# Sheet2.net
KiCad netlist of a schematic drawn in Altium Designer
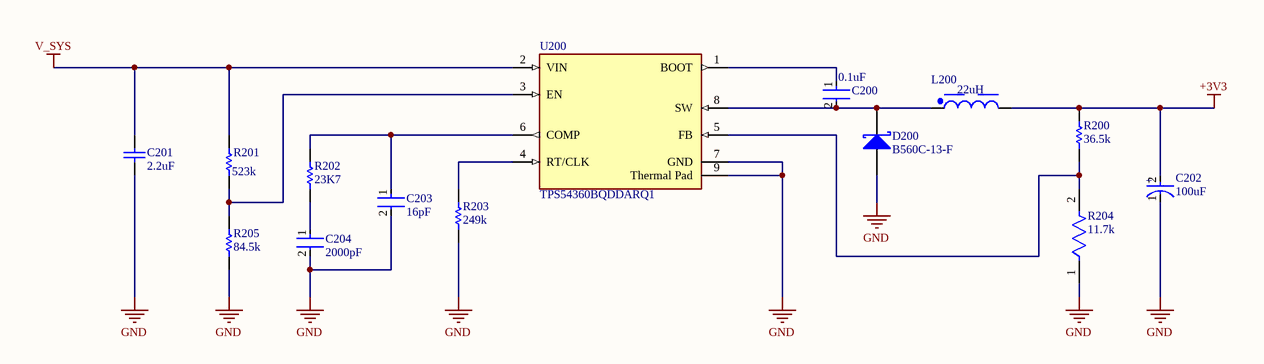
[diagram p0: Sheet2.SchDoc]

(export (version "E")
  (design (tool "Eeschema 10.0.6"))
  (components
    (comp (ref "C200")
      (value "0.1uF")
      (footprint "FP-CC0805-0_85-MFG")
      (description "CAP CER 0.1UF 50V X7R 0805")
      (fields (field (name "TOLERANCE") "0.1") (field (name "MANUFACTURER PART NUMBER") "CC0805KRX7R9BB104"))
      (libsource (lib "Altium Content Vault") (part "11868f565c42a9108669ba33697ecf6"))
    )
    (comp (ref "C201")
      (value "2.2uF")
      (footprint "CAPC3225X250X20LL40")
      (description "Chip Capacitor, 2.2 uF, +/- 10%, -55 to 125 degC, 1210 (3225 Metric), RoHS, Tape and Reel")
      (fields
        (field (name "PCN PART NUMBER") "MLCCPartNumberChange30/Nov/2012")
        (field (name "MANUFACTURER") "TDK")
      )
      (libsource (lib "Altium Content Vault") (part "CAP-NP-2"))
    )
    (comp (ref "C202")
      (value "100uF")
      (footprint "FP-POSCAP-D2E-MFG")
      (description "Molded Tantalum Polymer Capacitor 100uF 20% 6.3V life 2000Hours SMD 2917")
      (fields (field (name "TOLERANCE") "20%") (field (name "VOLTAGE") "6.3V"))
      (libsource (lib "Altium Content Vault") (part "84cdeef69100fe67ea2095257d64e1a"))
    )
    (comp (ref "C203")
      (value "16pF")
      (footprint "FP-C0603C-CF-MFG")
      (description "CAP CER 16PF 50V 5% NP0 0603")
      (fields
        (field (name "MANUFACTURER PART NUMBER") "C0603C160J5GACTU")
        (field (name "OCTOPART") "https://octopart.com/c0603c160j5gactu-kemet-9143816")
      )
      (libsource (lib "Altium Content Vault") (part "b4654b650e69147ec39a6b967a45e02"))
    )
    (comp (ref "C204")
      (value "2000pF")
      (footprint "FP-C0805C-DN-MFG")
      (description "CAP CER 2000PF 25V 5% NP0 0805")
      (fields
        (field (name "OCTOPART") "https://octopart.com/c0805c202j3gactu-kemet-11998870")
        (field (name "MANUFACTURER PART NUMBER") "C0805C202J3GACTU")
      )
      (libsource (lib "Altium Content Vault") (part "b4654b650e69147ec39a6b967a45e02"))
    )
    (comp (ref "D200")
      (value "B560C-13-F")
      (footprint "DIOD-B5X0C-2_M")
      (description "Schottky Barrier Rectifier, 5 A, 60 V, -55 to 125 degC, 2-Pin SMD, RoHS, Tape and Reel")
      (fields (field (name "MANUFACTURER") "DiodesIncorporated"))
      (libsource (lib "Altium Content Vault") (part "DSKY-KA-2"))
    )
    (comp (ref "L200")
      (value "22uH")
      (footprint "WE-TI_8095")
      (description "Inductor, 22Uh, Unshielded, 3A, Rad Rohs Compliant: Yes")
      (libsource (lib "Altium Content Vault") (part "Inductor - 2"))
    )
    (comp (ref "R200")
      (value "36.5k")
      (footprint "RESC0603X28X15ML05T05")
      (description "100mW Thick Film Resistors 75V ±1% ±100ppm/℃ 36.5kΩ 0603 Chip Resistor - Surface")
      (fields (field (name "MANUFACTURER") "Vishay Dale") (field (name "PART NUMBER") "CRCW020136K5FNED"))
      (libsource (lib "Altium Content Vault") (part "RES"))
    )
    (comp (ref "R201")
      (value "523k")
      (footprint "RESC1005X40X25NL05T10")
      (description "RES 523K OHM 1% 1/16W 0402")
      (fields (field (name "PART NUMBER") "RC0402FR-07523KL") (field (name "MANUFACTURER") "Yageo / Phycomp"))
      (libsource (lib "Altium Content Vault") (part "RES"))
    )
    (comp (ref "R202")
      (value "23K7")
      (footprint "RESC0201(0603)_M")
      (description "23K7 0.05W 1% 0201 (0603 Metric)  SMD")
      (fields (field (name "POWER") "0.05 W") (field (name "TOLERANCE") "1 %"))
      (libsource (lib "Altium Content Vault") (part "RES"))
    )
    (comp (ref "R203")
      (value "249k")
      (footprint "RESC0603X28X15LL05T05")
      (description "Res Thick Film 0603 2.2K Ohm 1% 0.1W(1/10W) ±100ppm/C SMD AutomoTEXASve T/R")
      (fields (field (name "PART NUMBER") "CRCW0201249KFKED") (field (name "MANUFACTURER") "Vishay Dale"))
      (libsource (lib "Altium Content Vault") (part "RES"))
    )
    (comp (ref "R204")
      (value "11.7k")
      (footprint "FP-RT0805-MFG")
      (description "RES 11.7K OHM 0.1% 1/8W 0805")
      (fields (field (name "TOLERANCE") "0.1%") (field (name "MANUFACTURER") "Yageo"))
      (libsource (lib "Altium Content Vault") (part "1029c3af85768c4190bb7ad29bc67b5"))
    )
    (comp (ref "R205")
      (value "84.5k")
      (footprint "RESC1005X40X25ML05T10")
      (description "RES 84.5K OHM 1% 1/16W 0402")
      (fields (field (name "MANUFACTURER") "Yageo / Phycomp") (field (name "PART NUMBER") "RC0402FR-0784K5L"))
      (libsource (lib "Altium Content Vault") (part "RES"))
    )
    (comp (ref "U200")
      (value "TPS54360BQDDARQ1")
      (footprint "FP-DDA0008E-MFG")
      (description "IC REG BCK SPLIT RAIL ADJ 8SOPWR")
      (fields
        (field (name "OCTOPART") "https://octopart.com/tps54360bqddarq1-texas+instruments-80336296")
        (field (name "MANUFACTURER") "Texas Instruments")
      )
      (libsource (lib "Altium Content Vault") (part "4212a49dfb3254156d8b0568d0e7c54"))
    )
  )
  (nets
    (net (code "1") (name "+3V3") (class "Default")
      (node (ref "C202") (pin "2") (pinfunction "A_2") (pintype "passive"))
      (node (ref "L200") (pin "2") (pinfunction "2_2") (pintype "passive"))
      (node (ref "R200") (pin "2") (pinfunction "2_2") (pintype "passive"))
    )
    (net (code "2") (name "GND") (class "Default")
      (node (ref "C201") (pin "1") (pinfunction "1_1") (pintype "passive"))
      (node (ref "C202") (pin "1") (pinfunction "C_1") (pintype "passive"))
      (node (ref "C203") (pin "2") (pinfunction "2_2") (pintype "passive"))
      (node (ref "C204") (pin "2") (pinfunction "2_2") (pintype "passive"))
      (node (ref "D200") (pin "2") (pinfunction "A_2") (pintype "passive"))
      (node (ref "R203") (pin "1") (pinfunction "1_1") (pintype "passive"))
      (node (ref "R204") (pin "1") (pinfunction "1_1") (pintype "passive"))
      (node (ref "R205") (pin "1") (pinfunction "1_1") (pintype "passive"))
      (node (ref "U200") (pin "7") (pinfunction "GND_7") (pintype "power_in"))
      (node (ref "U200") (pin "9") (pinfunction "Thermal_Pad_9") (pintype "power_in"))
    )
    (net (code "3") (name "Net-(C204-Pad1)") (class "Default")
      (node (ref "C204") (pin "1") (pinfunction "1_1") (pintype "passive"))
      (node (ref "R202") (pin "1") (pinfunction "1_1") (pintype "passive"))
    )
    (net (code "4") (name "Net-(D200-K)") (class "Default")
      (node (ref "C200") (pin "2") (pinfunction "2_2") (pintype "passive"))
      (node (ref "D200") (pin "1") (pinfunction "K_1") (pintype "passive"))
      (node (ref "L200") (pin "1") (pinfunction "1_1") (pintype "passive"))
      (node (ref "U200") (pin "8") (pinfunction "SW_8") (pintype "input"))
    )
    (net (code "5") (name "Net-(U200-BOOT)") (class "Default")
      (node (ref "C200") (pin "1") (pinfunction "1_1") (pintype "passive"))
      (node (ref "U200") (pin "1") (pinfunction "BOOT_1") (pintype "output"))
    )
    (net (code "6") (name "Net-(U200-COMP)") (class "Default")
      (node (ref "C203") (pin "1") (pinfunction "1_1") (pintype "passive"))
      (node (ref "R202") (pin "2") (pinfunction "2_2") (pintype "passive"))
      (node (ref "U200") (pin "6") (pinfunction "COMP_6") (pintype "output"))
    )
    (net (code "7") (name "Net-(U200-EN)") (class "Default")
      (node (ref "R201") (pin "1") (pinfunction "1_1") (pintype "passive"))
      (node (ref "R205") (pin "2") (pinfunction "2_2") (pintype "passive"))
      (node (ref "U200") (pin "3") (pinfunction "EN_3") (pintype "input"))
    )
    (net (code "8") (name "Net-(U200-FB)") (class "Default")
      (node (ref "R200") (pin "1") (pinfunction "1_1") (pintype "passive"))
      (node (ref "R204") (pin "2") (pinfunction "2_2") (pintype "passive"))
      (node (ref "U200") (pin "5") (pinfunction "FB_5") (pintype "input"))
    )
    (net (code "9") (name "Net-(U200-RT{slash}CLK)") (class "Default")
      (node (ref "R203") (pin "2") (pinfunction "2_2") (pintype "passive"))
      (node (ref "U200") (pin "4") (pinfunction "RT/CLK_4") (pintype "input"))
    )
    (net (code "10") (name "V_SYS") (class "Default")
      (node (ref "C201") (pin "2") (pinfunction "2_2") (pintype "passive"))
      (node (ref "R201") (pin "2") (pinfunction "2_2") (pintype "passive"))
      (node (ref "U200") (pin "2") (pinfunction "VIN_2") (pintype "input"))
    )
  )
)
